# Sparkfun_LilyPad-Switched-Battery_SVOP.net
KiCad netlist of a schematic drawn in EAGLE
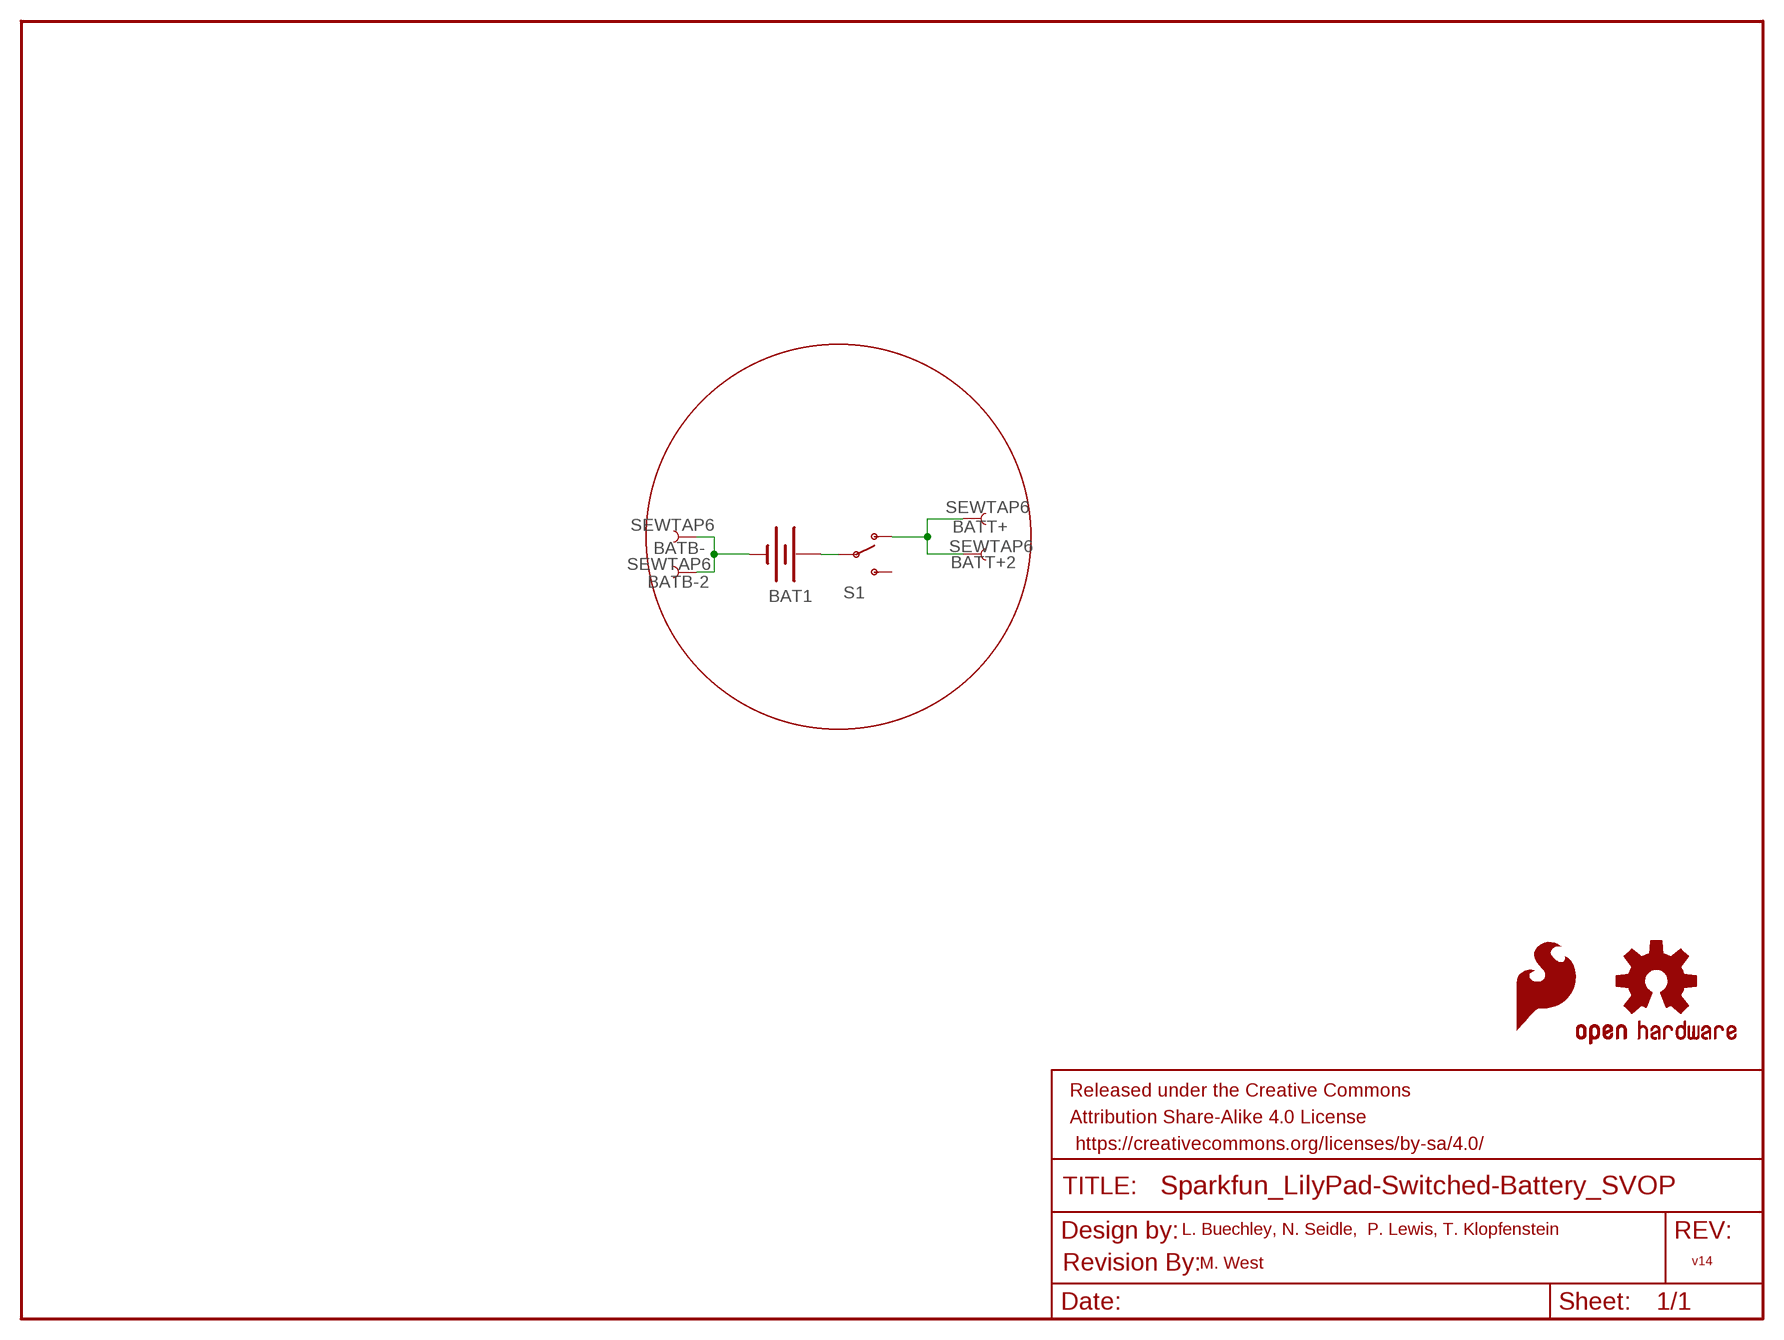
[diagram p0: schematic, sheet 1]

(export (version "E")
  (design (tool "Eeschema 10.0.6"))
  (components
    (comp (ref "BAT1")
      (value "20mm coincell")
      (footprint "eagle-import:BATTCON_20MM_4LEGS")
      (libsource (lib "eagle-import") (part "BATTERY20MM_4LEGS"))
    )
    (comp (ref "BATB-")
      (value "SEWTAP6")
      (footprint "eagle-import:PETAL-SMALL-2SIDE")
      (libsource (lib "eagle-import") (part "SEWTAP6"))
    )
    (comp (ref "BATB-2")
      (value "SEWTAP6")
      (footprint "eagle-import:PETAL-SMALL-2SIDE")
      (libsource (lib "eagle-import") (part "SEWTAP6"))
    )
    (comp (ref "BATT+")
      (value "SEWTAP6")
      (footprint "eagle-import:PETAL-SMALL-2SIDE")
      (libsource (lib "eagle-import") (part "SEWTAP6"))
    )
    (comp (ref "BATT+2")
      (value "SEWTAP6")
      (footprint "eagle-import:PETAL-SMALL-2SIDE")
      (libsource (lib "eagle-import") (part "SEWTAP6"))
    )
    (comp (ref "FRAME1")
      (value "FRAME-LETTER")
      (footprint "eagle-import:CREATIVE_COMMONS")
      (libsource (lib "eagle-import") (part "FRAME-LETTER"))
    )
    (comp (ref "LOGO1")
      (value "SFE_LOGO_FLAME.1_INCH")
      (footprint "eagle-import:SFE_LOGO_FLAME_.1")
      (libsource (lib "eagle-import") (part "SFE_LOGO_FLAME.1_INCH"))
    )
    (comp (ref "LOGO2")
      (value "OSHW-LOGOS")
      (footprint "eagle-import:OSHW-LOGO-S")
      (libsource (lib "eagle-import") (part "OSHW-LOGOS"))
    )
    (comp (ref "S1")
      (value "SWITCH-SPDTSMD")
      (footprint "eagle-import:AYZ0202")
      (libsource (lib "eagle-import") (part "SWITCH-SPDTSMD"))
    )
    (comp (ref "U$1")
      (value "REVISION")
      (footprint "eagle-import:REVISION")
      (libsource (lib "eagle-import") (part "REVISION"))
    )
  )
  (nets
    (net (code "1") (name "Net-(BAT1--)") (class "Default")
      (node (ref "BAT1") (pin "NEGATIVE") (pinfunction "-_NEGATIVE") (pintype "power_in"))
      (node (ref "BATB-") (pin "1") (pinfunction "1_1") (pintype "bidirectional"))
      (node (ref "BATB-2") (pin "1") (pinfunction "1_1") (pintype "bidirectional"))
    )
    (net (code "2") (name "Net-(S1-O)") (class "Default")
      (node (ref "BATT+") (pin "1") (pinfunction "1_1") (pintype "bidirectional"))
      (node (ref "BATT+2") (pin "1") (pinfunction "1_1") (pintype "bidirectional"))
      (node (ref "S1") (pin "1") (pinfunction "O_1") (pintype "passive"))
    )
    (net (code "3") (name "Net-(S1-P)") (class "Default")
      (node (ref "BAT1") (pin "POSITIVE@1") (pinfunction "+_POSITIVE@1") (pintype "power_in"))
      (node (ref "BAT1") (pin "POSITIVE@2") (pinfunction "+_POSITIVE@2") (pintype "power_in"))
      (node (ref "BAT1") (pin "POSITIVE@3") (pinfunction "+_POSITIVE@3") (pintype "power_in"))
      (node (ref "BAT1") (pin "POSITIVE@4") (pinfunction "+_POSITIVE@4") (pintype "power_in"))
      (node (ref "S1") (pin "2") (pinfunction "P_2") (pintype "passive"))
    )
    (net (code "4") (name "unconnected-(S1-S-Pad3)") (class "Default")
      (node (ref "S1") (pin "3") (pinfunction "S_3") (pintype "passive"))
    )
  )
)
